# vectrex.net
KiCad netlist of a schematic drawn in EAGLE
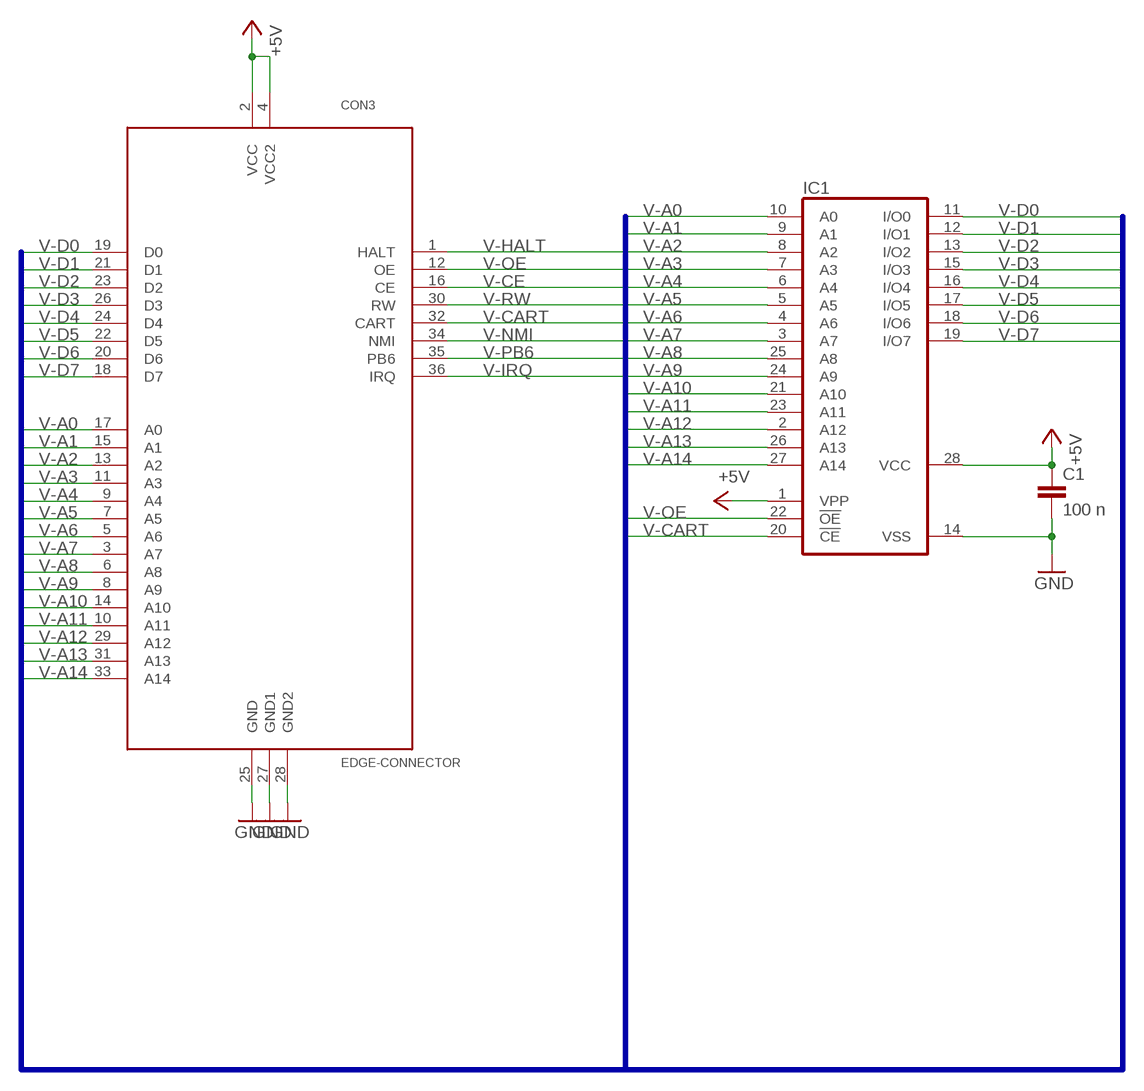
[diagram p0: schematic, sheet 1]

(export (version "E")
  (design (tool "Eeschema 10.0.6"))
  (components
    (comp (ref "C1")
      (value "100 n")
      (footprint "eagle-import:C050-045X075")
      (libsource (lib "eagle-import") (part "C-EU050-045X075"))
    )
    (comp (ref "CON3")
      (value "EDGE-CONNECTOR")
      (footprint "eagle-import:EDGE-CONNECTOR")
      (libsource (lib "eagle-import") (part "EDGE-CONNECTOR"))
    )
    (comp (ref "IC1")
      (value "27C256AG")
      (footprint "eagle-import:DIL28-6")
      (libsource (lib "eagle-import") (part "27C256AG"))
    )
  )
  (nets
    (net (code "1") (name "+5V") (class "Default")
      (node (ref "C1") (pin "1") (pinfunction "1_1") (pintype "passive"))
      (node (ref "CON3") (pin "2") (pinfunction "VCC_2") (pintype "bidirectional"))
      (node (ref "CON3") (pin "4") (pinfunction "VCC2_4") (pintype "bidirectional"))
      (node (ref "IC1") (pin "1") (pinfunction "VPP_1") (pintype "input"))
      (node (ref "IC1") (pin "28") (pinfunction "VCC_28") (pintype "power_in"))
    )
    (net (code "2") (name "/V-A0") (class "Default")
      (node (ref "CON3") (pin "17") (pinfunction "A0_17") (pintype "bidirectional"))
      (node (ref "IC1") (pin "10") (pinfunction "A0_10") (pintype "input"))
    )
    (net (code "3") (name "/V-A1") (class "Default")
      (node (ref "CON3") (pin "15") (pinfunction "A1_15") (pintype "bidirectional"))
      (node (ref "IC1") (pin "9") (pinfunction "A1_9") (pintype "input"))
    )
    (net (code "4") (name "/V-A2") (class "Default")
      (node (ref "CON3") (pin "13") (pinfunction "A2_13") (pintype "bidirectional"))
      (node (ref "IC1") (pin "8") (pinfunction "A2_8") (pintype "input"))
    )
    (net (code "5") (name "/V-A3") (class "Default")
      (node (ref "CON3") (pin "11") (pinfunction "A3_11") (pintype "bidirectional"))
      (node (ref "IC1") (pin "7") (pinfunction "A3_7") (pintype "input"))
    )
    (net (code "6") (name "/V-A4") (class "Default")
      (node (ref "CON3") (pin "9") (pinfunction "A4_9") (pintype "bidirectional"))
      (node (ref "IC1") (pin "6") (pinfunction "A4_6") (pintype "input"))
    )
    (net (code "7") (name "/V-A5") (class "Default")
      (node (ref "CON3") (pin "7") (pinfunction "A5_7") (pintype "bidirectional"))
      (node (ref "IC1") (pin "5") (pinfunction "A5_5") (pintype "input"))
    )
    (net (code "8") (name "/V-A6") (class "Default")
      (node (ref "CON3") (pin "5") (pinfunction "A6_5") (pintype "bidirectional"))
      (node (ref "IC1") (pin "4") (pinfunction "A6_4") (pintype "input"))
    )
    (net (code "9") (name "/V-A7") (class "Default")
      (node (ref "CON3") (pin "3") (pinfunction "A7_3") (pintype "bidirectional"))
      (node (ref "IC1") (pin "3") (pinfunction "A7_3") (pintype "input"))
    )
    (net (code "10") (name "/V-A8") (class "Default")
      (node (ref "CON3") (pin "6") (pinfunction "A8_6") (pintype "bidirectional"))
      (node (ref "IC1") (pin "25") (pinfunction "A8_25") (pintype "input"))
    )
    (net (code "11") (name "/V-A9") (class "Default")
      (node (ref "CON3") (pin "8") (pinfunction "A9_8") (pintype "bidirectional"))
      (node (ref "IC1") (pin "24") (pinfunction "A9_24") (pintype "input"))
    )
    (net (code "12") (name "/V-A10") (class "Default")
      (node (ref "CON3") (pin "14") (pinfunction "A10_14") (pintype "bidirectional"))
      (node (ref "IC1") (pin "21") (pinfunction "A10_21") (pintype "input"))
    )
    (net (code "13") (name "/V-A11") (class "Default")
      (node (ref "CON3") (pin "10") (pinfunction "A11_10") (pintype "bidirectional"))
      (node (ref "IC1") (pin "23") (pinfunction "A11_23") (pintype "input"))
    )
    (net (code "14") (name "/V-A12") (class "Default")
      (node (ref "CON3") (pin "29") (pinfunction "A12_29") (pintype "bidirectional"))
      (node (ref "IC1") (pin "2") (pinfunction "A12_2") (pintype "input"))
    )
    (net (code "15") (name "/V-A13") (class "Default")
      (node (ref "CON3") (pin "31") (pinfunction "A13_31") (pintype "bidirectional"))
      (node (ref "IC1") (pin "26") (pinfunction "A13_26") (pintype "input"))
    )
    (net (code "16") (name "/V-A14") (class "Default")
      (node (ref "CON3") (pin "33") (pinfunction "A14_33") (pintype "bidirectional"))
      (node (ref "IC1") (pin "27") (pinfunction "A14_27") (pintype "input"))
    )
    (net (code "17") (name "/V-CART") (class "Default")
      (node (ref "CON3") (pin "32") (pinfunction "CART_32") (pintype "bidirectional"))
      (node (ref "IC1") (pin "20") (pinfunction "~{CE}_20") (pintype "input"))
    )
    (net (code "18") (name "/V-CE") (class "Default")
      (node (ref "CON3") (pin "16") (pinfunction "CE_16") (pintype "bidirectional"))
    )
    (net (code "19") (name "/V-D0") (class "Default")
      (node (ref "CON3") (pin "19") (pinfunction "D0_19") (pintype "bidirectional"))
      (node (ref "IC1") (pin "11") (pinfunction "I/O0_11") (pintype "tri_state"))
    )
    (net (code "20") (name "/V-D1") (class "Default")
      (node (ref "CON3") (pin "21") (pinfunction "D1_21") (pintype "bidirectional"))
      (node (ref "IC1") (pin "12") (pinfunction "I/O1_12") (pintype "tri_state"))
    )
    (net (code "21") (name "/V-D2") (class "Default")
      (node (ref "CON3") (pin "23") (pinfunction "D2_23") (pintype "bidirectional"))
      (node (ref "IC1") (pin "13") (pinfunction "I/O2_13") (pintype "tri_state"))
    )
    (net (code "22") (name "/V-D3") (class "Default")
      (node (ref "CON3") (pin "26") (pinfunction "D3_26") (pintype "bidirectional"))
      (node (ref "IC1") (pin "15") (pinfunction "I/O3_15") (pintype "tri_state"))
    )
    (net (code "23") (name "/V-D4") (class "Default")
      (node (ref "CON3") (pin "24") (pinfunction "D4_24") (pintype "bidirectional"))
      (node (ref "IC1") (pin "16") (pinfunction "I/O4_16") (pintype "tri_state"))
    )
    (net (code "24") (name "/V-D5") (class "Default")
      (node (ref "CON3") (pin "22") (pinfunction "D5_22") (pintype "bidirectional"))
      (node (ref "IC1") (pin "17") (pinfunction "I/O5_17") (pintype "tri_state"))
    )
    (net (code "25") (name "/V-D6") (class "Default")
      (node (ref "CON3") (pin "20") (pinfunction "D6_20") (pintype "bidirectional"))
      (node (ref "IC1") (pin "18") (pinfunction "I/O6_18") (pintype "tri_state"))
    )
    (net (code "26") (name "/V-D7") (class "Default")
      (node (ref "CON3") (pin "18") (pinfunction "D7_18") (pintype "bidirectional"))
      (node (ref "IC1") (pin "19") (pinfunction "I/O7_19") (pintype "tri_state"))
    )
    (net (code "27") (name "/V-HALT") (class "Default")
      (node (ref "CON3") (pin "1") (pinfunction "HALT_1") (pintype "bidirectional"))
    )
    (net (code "28") (name "/V-IRQ") (class "Default")
      (node (ref "CON3") (pin "36") (pinfunction "IRQ_36") (pintype "bidirectional"))
    )
    (net (code "29") (name "/V-NMI") (class "Default")
      (node (ref "CON3") (pin "34") (pinfunction "NMI_34") (pintype "bidirectional"))
    )
    (net (code "30") (name "/V-OE") (class "Default")
      (node (ref "CON3") (pin "12") (pinfunction "OE_12") (pintype "bidirectional"))
      (node (ref "IC1") (pin "22") (pinfunction "~{OE}_22") (pintype "input"))
    )
    (net (code "31") (name "/V-PB6") (class "Default")
      (node (ref "CON3") (pin "35") (pinfunction "PB6_35") (pintype "bidirectional"))
    )
    (net (code "32") (name "/V-RW") (class "Default")
      (node (ref "CON3") (pin "30") (pinfunction "RW_30") (pintype "bidirectional"))
    )
    (net (code "33") (name "GND") (class "Default")
      (node (ref "C1") (pin "2") (pinfunction "2_2") (pintype "passive"))
      (node (ref "CON3") (pin "25") (pinfunction "GND_25") (pintype "bidirectional"))
      (node (ref "CON3") (pin "27") (pinfunction "GND1_27") (pintype "bidirectional"))
      (node (ref "CON3") (pin "28") (pinfunction "GND2_28") (pintype "bidirectional"))
      (node (ref "IC1") (pin "14") (pinfunction "VSS_14") (pintype "power_in"))
    )
  )
)
